# cpx-synth2-B.net
KiCad netlist of a schematic drawn in EAGLE
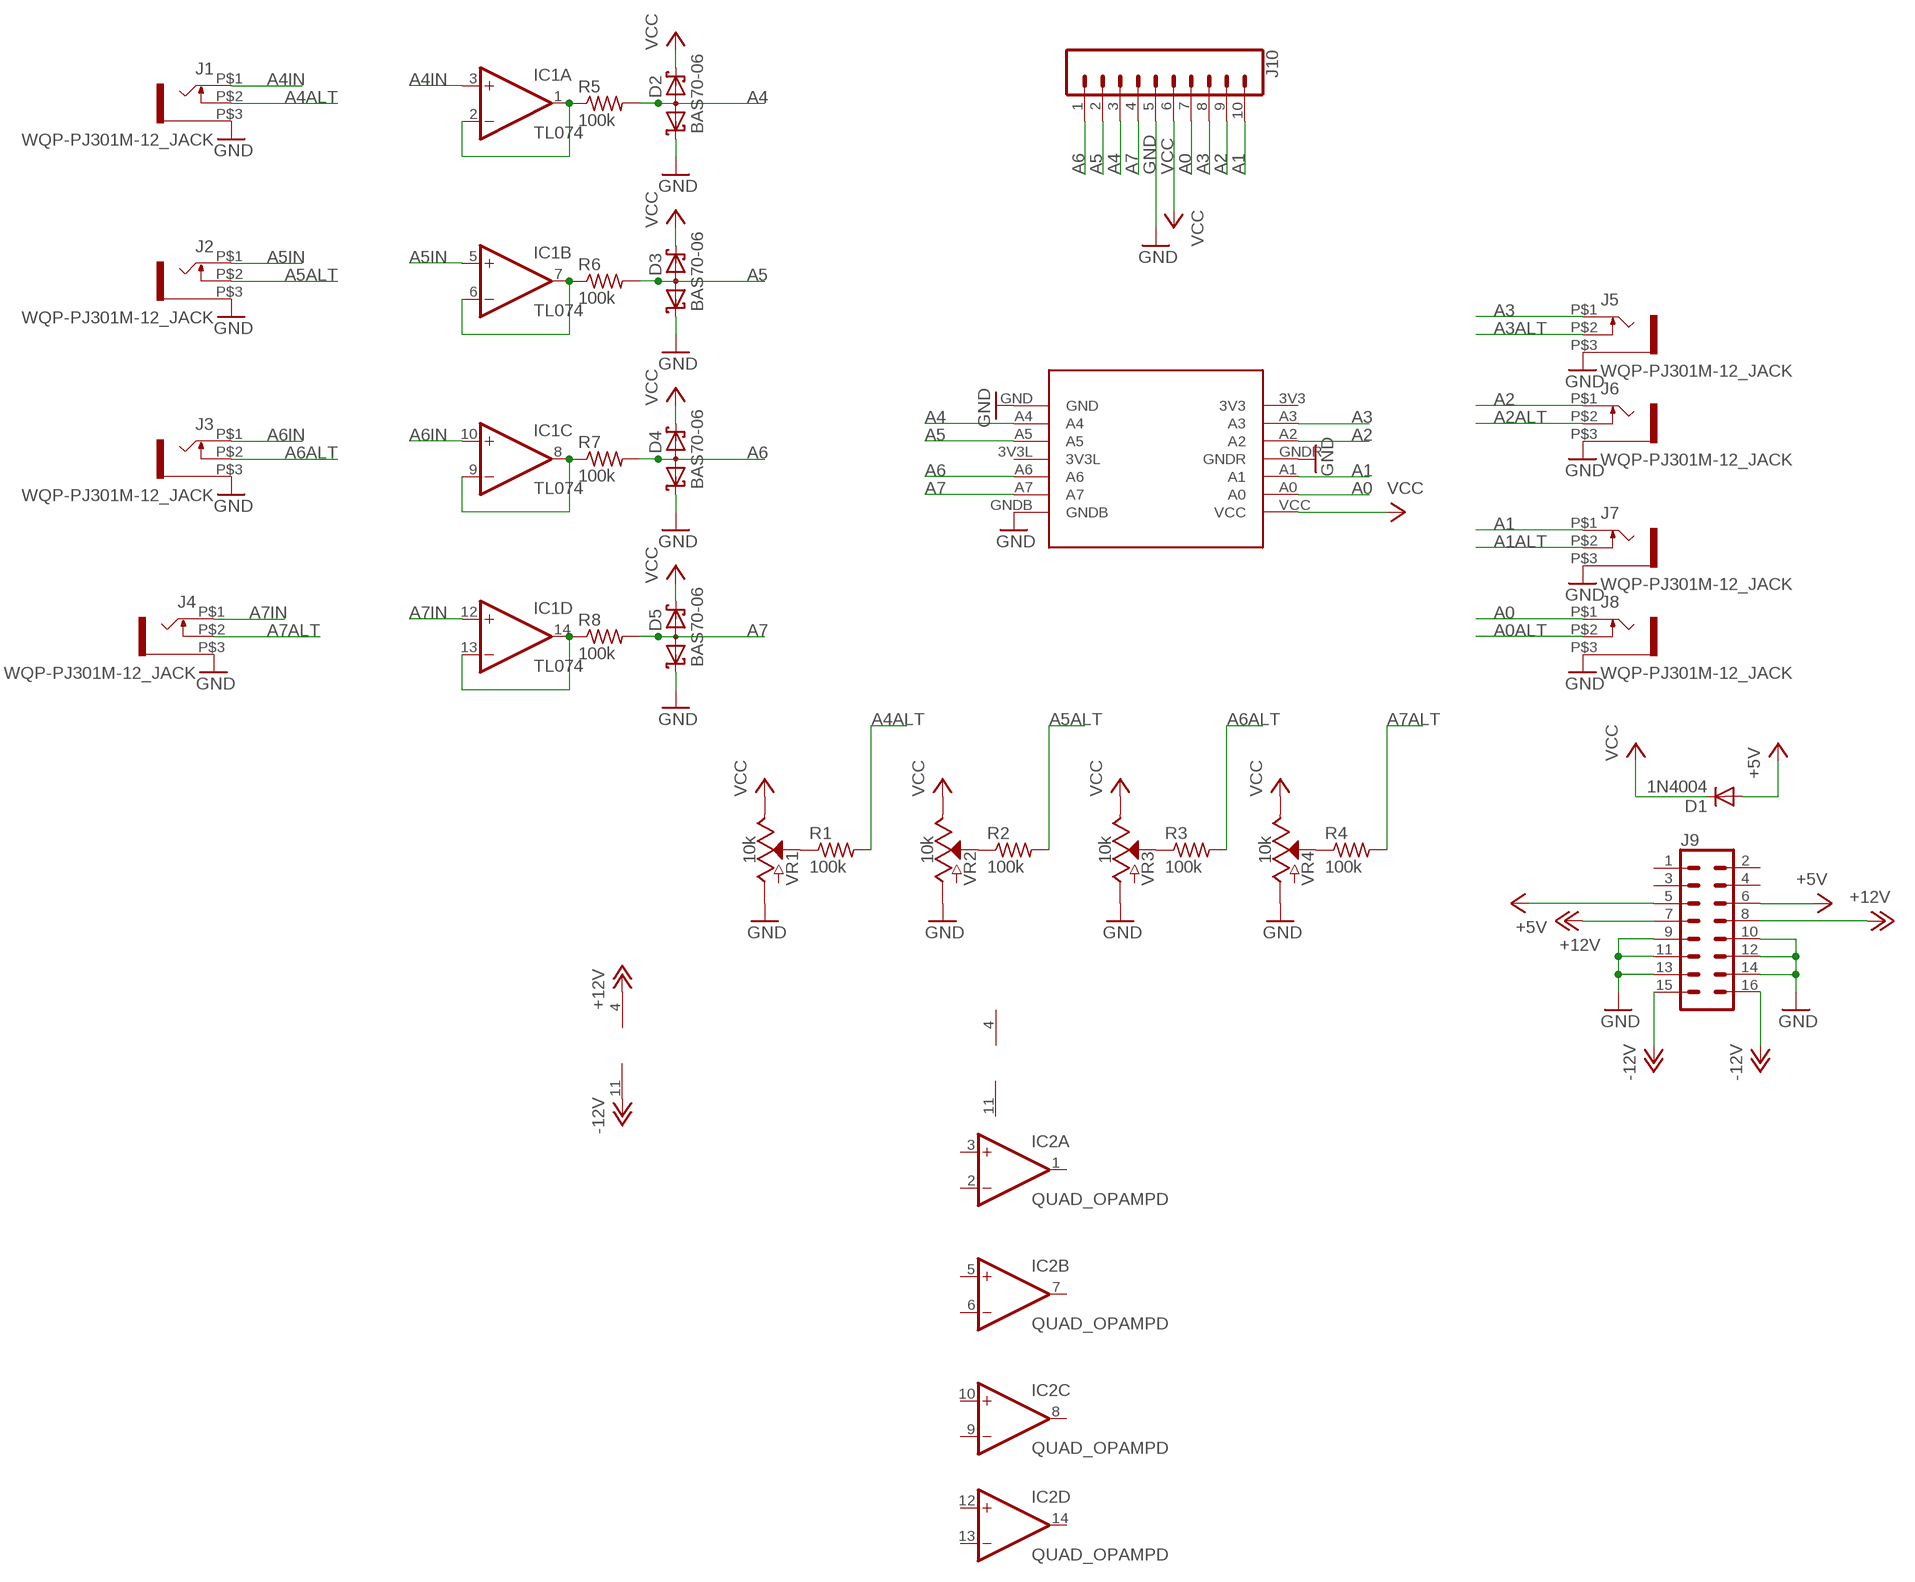
[diagram p0: schematic, sheet 1]

(export (version "E")
  (design (tool "Eeschema 10.0.6"))
  (components
    (comp (ref "D1")
      (value "1N4004")
      (footprint "eagle-import:DO41-10")
      (libsource (lib "eagle-import") (part "1N4004"))
    )
    (comp (ref "D2")
      (value "BAS70-06")
      (footprint "eagle-import:SOT23")
      (libsource (lib "eagle-import") (part "BAS70-06"))
    )
    (comp (ref "D3")
      (value "BAS70-06")
      (footprint "eagle-import:SOT23")
      (libsource (lib "eagle-import") (part "BAS70-06"))
    )
    (comp (ref "D4")
      (value "BAS70-06")
      (footprint "eagle-import:SOT23")
      (libsource (lib "eagle-import") (part "BAS70-06"))
    )
    (comp (ref "D5")
      (value "BAS70-06")
      (footprint "eagle-import:SOT23")
      (libsource (lib "eagle-import") (part "BAS70-06"))
    )
    (comp (ref "IC1")
      (value "TL074")
      (footprint "eagle-import:SO14")
      (libsource (lib "eagle-import") (part "QUAD_OPAMPD"))
    )
    (comp (ref "IC2")
      (value "QUAD_OPAMPD")
      (footprint "eagle-import:SO14")
      (libsource (lib "eagle-import") (part "QUAD_OPAMPD"))
    )
    (comp (ref "J1")
      (value "WQP-PJ301M-12_JACK")
      (footprint "eagle-import:WQP-PJ301M-12_JACK")
      (libsource (lib "eagle-import") (part "WQP-PJ301M-12_JACK"))
    )
    (comp (ref "J2")
      (value "WQP-PJ301M-12_JACK")
      (footprint "eagle-import:WQP-PJ301M-12_JACK")
      (libsource (lib "eagle-import") (part "WQP-PJ301M-12_JACK"))
    )
    (comp (ref "J3")
      (value "WQP-PJ301M-12_JACK")
      (footprint "eagle-import:WQP-PJ301M-12_JACK")
      (libsource (lib "eagle-import") (part "WQP-PJ301M-12_JACK"))
    )
    (comp (ref "J4")
      (value "WQP-PJ301M-12_JACK")
      (footprint "eagle-import:WQP-PJ301M-12_JACK")
      (libsource (lib "eagle-import") (part "WQP-PJ301M-12_JACK"))
    )
    (comp (ref "J5")
      (value "WQP-PJ301M-12_JACK")
      (footprint "eagle-import:WQP-PJ301M-12_JACK")
      (libsource (lib "eagle-import") (part "WQP-PJ301M-12_JACK"))
    )
    (comp (ref "J6")
      (value "WQP-PJ301M-12_JACK")
      (footprint "eagle-import:WQP-PJ301M-12_JACK")
      (libsource (lib "eagle-import") (part "WQP-PJ301M-12_JACK"))
    )
    (comp (ref "J7")
      (value "WQP-PJ301M-12_JACK")
      (footprint "eagle-import:WQP-PJ301M-12_JACK")
      (libsource (lib "eagle-import") (part "WQP-PJ301M-12_JACK"))
    )
    (comp (ref "J8")
      (value "WQP-PJ301M-12_JACK")
      (footprint "eagle-import:WQP-PJ301M-12_JACK")
      (libsource (lib "eagle-import") (part "WQP-PJ301M-12_JACK"))
    )
    (comp (ref "J9")
      (value "CONN_08X2")
      (footprint "eagle-import:2X8")
      (libsource (lib "eagle-import") (part "CONN_08X2"))
    )
    (comp (ref "J10")
      (value "CONN_10\"")
      (footprint "eagle-import:1X10")
      (libsource (lib "eagle-import") (part "CONN_10{dblquote}"))
    )
    (comp (ref "R1")
      (value "100k")
      (footprint "eagle-import:R0603")
      (libsource (lib "eagle-import") (part "R-US_R0603"))
    )
    (comp (ref "R2")
      (value "100k")
      (footprint "eagle-import:R0603")
      (libsource (lib "eagle-import") (part "R-US_R0603"))
    )
    (comp (ref "R3")
      (value "100k")
      (footprint "eagle-import:R0603")
      (libsource (lib "eagle-import") (part "R-US_R0603"))
    )
    (comp (ref "R4")
      (value "100k")
      (footprint "eagle-import:R0603")
      (libsource (lib "eagle-import") (part "R-US_R0603"))
    )
    (comp (ref "R5")
      (value "100k")
      (footprint "eagle-import:R0603")
      (libsource (lib "eagle-import") (part "R-US_R0603"))
    )
    (comp (ref "R6")
      (value "100k")
      (footprint "eagle-import:R0603")
      (libsource (lib "eagle-import") (part "R-US_R0603"))
    )
    (comp (ref "R7")
      (value "100k")
      (footprint "eagle-import:R0603")
      (libsource (lib "eagle-import") (part "R-US_R0603"))
    )
    (comp (ref "R8")
      (value "100k")
      (footprint "eagle-import:R0603")
      (libsource (lib "eagle-import") (part "R-US_R0603"))
    )
    (comp (ref "U1")
      (value "CIRCUITPLAYGROUNDEXPRESS")
      (footprint "eagle-import:CIRCUITPLAYGROUNDEXPRESS")
      (libsource (lib "eagle-import") (part "CIRCUITPLAYGROUNDEXPRESS"))
    )
    (comp (ref "VR1")
      (value "10k")
      (footprint "eagle-import:POT-PTH-ALPS-KIT")
      (libsource (lib "eagle-import") (part "POTENTIOMETER-PTH-9MM-1/20W-20%-KIT"))
    )
    (comp (ref "VR2")
      (value "10k")
      (footprint "eagle-import:POT-PTH-ALPS-KIT")
      (libsource (lib "eagle-import") (part "POTENTIOMETER-PTH-9MM-1/20W-20%-KIT"))
    )
    (comp (ref "VR3")
      (value "10k")
      (footprint "eagle-import:POT-PTH-ALPS-KIT")
      (libsource (lib "eagle-import") (part "POTENTIOMETER-PTH-9MM-1/20W-20%-KIT"))
    )
    (comp (ref "VR4")
      (value "10k")
      (footprint "eagle-import:POT-PTH-ALPS-KIT")
      (libsource (lib "eagle-import") (part "POTENTIOMETER-PTH-9MM-1/20W-20%-KIT"))
    )
  )
  (nets
    (net (code "1") (name "+5V") (class "Default")
      (node (ref "D1") (pin "A") (pinfunction "A_A") (pintype "passive"))
      (node (ref "J9") (pin "5") (pinfunction "5_5") (pintype "passive"))
      (node (ref "J9") (pin "6") (pinfunction "6_6") (pintype "passive"))
    )
    (net (code "2") (name "+12V") (class "Default")
      (node (ref "IC1") (pin "4") (pinfunction "V+_4") (pintype "power_in"))
      (node (ref "J9") (pin "7") (pinfunction "7_7") (pintype "passive"))
      (node (ref "J9") (pin "8") (pinfunction "8_8") (pintype "passive"))
    )
    (net (code "3") (name "-12V") (class "Default")
      (node (ref "IC1") (pin "11") (pinfunction "V-_11") (pintype "power_in"))
      (node (ref "J9") (pin "15") (pinfunction "15_15") (pintype "passive"))
      (node (ref "J9") (pin "16") (pinfunction "16_16") (pintype "passive"))
    )
    (net (code "4") (name "/A0") (class "Default")
      (node (ref "J10") (pin "7") (pinfunction "7_7") (pintype "passive"))
      (node (ref "J8") (pin "P$1") (pinfunction "2_P$1") (pintype "passive"))
      (node (ref "U1") (pin "A0") (pinfunction "A0_A0") (pintype "bidirectional"))
    )
    (net (code "5") (name "/A0ALT") (class "Default")
      (node (ref "J8") (pin "P$2") (pinfunction "3_P$2") (pintype "passive"))
    )
    (net (code "6") (name "/A1") (class "Default")
      (node (ref "J10") (pin "10") (pinfunction "10_10") (pintype "passive"))
      (node (ref "J7") (pin "P$1") (pinfunction "2_P$1") (pintype "passive"))
      (node (ref "U1") (pin "A1") (pinfunction "A1_A1") (pintype "bidirectional"))
    )
    (net (code "7") (name "/A1ALT") (class "Default")
      (node (ref "J7") (pin "P$2") (pinfunction "3_P$2") (pintype "passive"))
    )
    (net (code "8") (name "/A2") (class "Default")
      (node (ref "J10") (pin "9") (pinfunction "9_9") (pintype "passive"))
      (node (ref "J6") (pin "P$1") (pinfunction "2_P$1") (pintype "passive"))
      (node (ref "U1") (pin "A2") (pinfunction "A2_A2") (pintype "bidirectional"))
    )
    (net (code "9") (name "/A2ALT") (class "Default")
      (node (ref "J6") (pin "P$2") (pinfunction "3_P$2") (pintype "passive"))
    )
    (net (code "10") (name "/A3") (class "Default")
      (node (ref "J10") (pin "8") (pinfunction "8_8") (pintype "passive"))
      (node (ref "J5") (pin "P$1") (pinfunction "2_P$1") (pintype "passive"))
      (node (ref "U1") (pin "A3") (pinfunction "A3_A3") (pintype "bidirectional"))
    )
    (net (code "11") (name "/A3ALT") (class "Default")
      (node (ref "J5") (pin "P$2") (pinfunction "3_P$2") (pintype "passive"))
    )
    (net (code "12") (name "/A4") (class "Default")
      (node (ref "D2") (pin "3") (pinfunction "AA_3") (pintype "passive"))
      (node (ref "J10") (pin "3") (pinfunction "3_3") (pintype "passive"))
      (node (ref "R5") (pin "2") (pinfunction "2_2") (pintype "passive"))
      (node (ref "U1") (pin "A4") (pinfunction "A4_A4") (pintype "bidirectional"))
    )
    (net (code "13") (name "/A4ALT") (class "Default")
      (node (ref "J1") (pin "P$2") (pinfunction "3_P$2") (pintype "passive"))
      (node (ref "R1") (pin "2") (pinfunction "2_2") (pintype "passive"))
    )
    (net (code "14") (name "/A4IN") (class "Default")
      (node (ref "IC1") (pin "3") (pinfunction "+IN_3") (pintype "input"))
      (node (ref "J1") (pin "P$1") (pinfunction "2_P$1") (pintype "passive"))
    )
    (net (code "15") (name "/A5") (class "Default")
      (node (ref "D3") (pin "3") (pinfunction "AA_3") (pintype "passive"))
      (node (ref "J10") (pin "2") (pinfunction "2_2") (pintype "passive"))
      (node (ref "R6") (pin "2") (pinfunction "2_2") (pintype "passive"))
      (node (ref "U1") (pin "A5") (pinfunction "A5_A5") (pintype "bidirectional"))
    )
    (net (code "16") (name "/A5ALT") (class "Default")
      (node (ref "J2") (pin "P$2") (pinfunction "3_P$2") (pintype "passive"))
      (node (ref "R2") (pin "2") (pinfunction "2_2") (pintype "passive"))
    )
    (net (code "17") (name "/A5IN") (class "Default")
      (node (ref "IC1") (pin "5") (pinfunction "+IN_5") (pintype "input"))
      (node (ref "J2") (pin "P$1") (pinfunction "2_P$1") (pintype "passive"))
    )
    (net (code "18") (name "/A6") (class "Default")
      (node (ref "D4") (pin "3") (pinfunction "AA_3") (pintype "passive"))
      (node (ref "J10") (pin "1") (pinfunction "1_1") (pintype "passive"))
      (node (ref "R7") (pin "2") (pinfunction "2_2") (pintype "passive"))
      (node (ref "U1") (pin "A6") (pinfunction "A6_A6") (pintype "bidirectional"))
    )
    (net (code "19") (name "/A6ALT") (class "Default")
      (node (ref "J3") (pin "P$2") (pinfunction "3_P$2") (pintype "passive"))
      (node (ref "R3") (pin "2") (pinfunction "2_2") (pintype "passive"))
    )
    (net (code "20") (name "/A6IN") (class "Default")
      (node (ref "IC1") (pin "10") (pinfunction "+IN_10") (pintype "input"))
      (node (ref "J3") (pin "P$1") (pinfunction "2_P$1") (pintype "passive"))
    )
    (net (code "21") (name "/A7") (class "Default")
      (node (ref "D5") (pin "3") (pinfunction "AA_3") (pintype "passive"))
      (node (ref "J10") (pin "4") (pinfunction "4_4") (pintype "passive"))
      (node (ref "R8") (pin "2") (pinfunction "2_2") (pintype "passive"))
      (node (ref "U1") (pin "A7") (pinfunction "A7_A7") (pintype "bidirectional"))
    )
    (net (code "22") (name "/A7ALT") (class "Default")
      (node (ref "J4") (pin "P$2") (pinfunction "3_P$2") (pintype "passive"))
      (node (ref "R4") (pin "2") (pinfunction "2_2") (pintype "passive"))
    )
    (net (code "23") (name "/A7IN") (class "Default")
      (node (ref "IC1") (pin "12") (pinfunction "+IN_12") (pintype "input"))
      (node (ref "J4") (pin "P$1") (pinfunction "2_P$1") (pintype "passive"))
    )
    (net (code "24") (name "/V+") (class "Default")
      (node (ref "IC2") (pin "4") (pinfunction "V+_4") (pintype "power_in"))
    )
    (net (code "25") (name "/V-") (class "Default")
      (node (ref "IC2") (pin "11") (pinfunction "V-_11") (pintype "power_in"))
    )
    (net (code "26") (name "GND") (class "Default")
      (node (ref "D2") (pin "1") (pinfunction "K1_1") (pintype "passive"))
      (node (ref "D3") (pin "1") (pinfunction "K1_1") (pintype "passive"))
      (node (ref "D4") (pin "1") (pinfunction "K1_1") (pintype "passive"))
      (node (ref "D5") (pin "1") (pinfunction "K1_1") (pintype "passive"))
      (node (ref "J1") (pin "P$3") (pinfunction "1_P$3") (pintype "passive"))
      (node (ref "J10") (pin "5") (pinfunction "5_5") (pintype "passive"))
      (node (ref "J2") (pin "P$3") (pinfunction "1_P$3") (pintype "passive"))
      (node (ref "J3") (pin "P$3") (pinfunction "1_P$3") (pintype "passive"))
      (node (ref "J4") (pin "P$3") (pinfunction "1_P$3") (pintype "passive"))
      (node (ref "J5") (pin "P$3") (pinfunction "1_P$3") (pintype "passive"))
      (node (ref "J6") (pin "P$3") (pinfunction "1_P$3") (pintype "passive"))
      (node (ref "J7") (pin "P$3") (pinfunction "1_P$3") (pintype "passive"))
      (node (ref "J8") (pin "P$3") (pinfunction "1_P$3") (pintype "passive"))
      (node (ref "J9") (pin "10") (pinfunction "10_10") (pintype "passive"))
      (node (ref "J9") (pin "11") (pinfunction "11_11") (pintype "passive"))
      (node (ref "J9") (pin "12") (pinfunction "12_12") (pintype "passive"))
      (node (ref "J9") (pin "13") (pinfunction "13_13") (pintype "passive"))
      (node (ref "J9") (pin "14") (pinfunction "14_14") (pintype "passive"))
      (node (ref "J9") (pin "9") (pinfunction "9_9") (pintype "passive"))
      (node (ref "U1") (pin "GND") (pinfunction "GND_GND") (pintype "bidirectional"))
      (node (ref "U1") (pin "GNDB") (pinfunction "GNDB_GNDB") (pintype "bidirectional"))
      (node (ref "U1") (pin "GNDR") (pinfunction "GNDR_GNDR") (pintype "bidirectional"))
      (node (ref "VR1") (pin "P$3") (pinfunction "A_P$3") (pintype "passive"))
      (node (ref "VR2") (pin "P$3") (pinfunction "A_P$3") (pintype "passive"))
      (node (ref "VR3") (pin "P$3") (pinfunction "A_P$3") (pintype "passive"))
      (node (ref "VR4") (pin "P$3") (pinfunction "A_P$3") (pintype "passive"))
    )
    (net (code "27") (name "Net-(IC1A--IN)") (class "Default")
      (node (ref "IC1") (pin "1") (pinfunction "OUT_1") (pintype "output"))
      (node (ref "IC1") (pin "2") (pinfunction "-IN_2") (pintype "input"))
      (node (ref "R5") (pin "1") (pinfunction "1_1") (pintype "passive"))
    )
    (net (code "28") (name "Net-(IC1B--IN)") (class "Default")
      (node (ref "IC1") (pin "6") (pinfunction "-IN_6") (pintype "input"))
      (node (ref "IC1") (pin "7") (pinfunction "OUT_7") (pintype "output"))
      (node (ref "R6") (pin "1") (pinfunction "1_1") (pintype "passive"))
    )
    (net (code "29") (name "Net-(IC1C--IN)") (class "Default")
      (node (ref "IC1") (pin "8") (pinfunction "OUT_8") (pintype "output"))
      (node (ref "IC1") (pin "9") (pinfunction "-IN_9") (pintype "input"))
      (node (ref "R7") (pin "1") (pinfunction "1_1") (pintype "passive"))
    )
    (net (code "30") (name "Net-(IC1D--IN)") (class "Default")
      (node (ref "IC1") (pin "13") (pinfunction "-IN_13") (pintype "input"))
      (node (ref "IC1") (pin "14") (pinfunction "OUT_14") (pintype "output"))
      (node (ref "R8") (pin "1") (pinfunction "1_1") (pintype "passive"))
    )
    (net (code "31") (name "Net-(VR1-S)") (class "Default")
      (node (ref "R1") (pin "1") (pinfunction "1_1") (pintype "passive"))
      (node (ref "VR1") (pin "P$2") (pinfunction "S_P$2") (pintype "passive"))
    )
    (net (code "32") (name "Net-(VR2-S)") (class "Default")
      (node (ref "R2") (pin "1") (pinfunction "1_1") (pintype "passive"))
      (node (ref "VR2") (pin "P$2") (pinfunction "S_P$2") (pintype "passive"))
    )
    (net (code "33") (name "Net-(VR3-S)") (class "Default")
      (node (ref "R3") (pin "1") (pinfunction "1_1") (pintype "passive"))
      (node (ref "VR3") (pin "P$2") (pinfunction "S_P$2") (pintype "passive"))
    )
    (net (code "34") (name "Net-(VR4-S)") (class "Default")
      (node (ref "R4") (pin "1") (pinfunction "1_1") (pintype "passive"))
      (node (ref "VR4") (pin "P$2") (pinfunction "S_P$2") (pintype "passive"))
    )
    (net (code "35") (name "VCC") (class "Default")
      (node (ref "D1") (pin "C") (pinfunction "C_C") (pintype "passive"))
      (node (ref "D2") (pin "2") (pinfunction "K2_2") (pintype "passive"))
      (node (ref "D3") (pin "2") (pinfunction "K2_2") (pintype "passive"))
      (node (ref "D4") (pin "2") (pinfunction "K2_2") (pintype "passive"))
      (node (ref "D5") (pin "2") (pinfunction "K2_2") (pintype "passive"))
      (node (ref "J10") (pin "6") (pinfunction "6_6") (pintype "passive"))
      (node (ref "U1") (pin "VCC") (pinfunction "VCC_VCC") (pintype "bidirectional"))
      (node (ref "VR1") (pin "P$1") (pinfunction "E_P$1") (pintype "passive"))
      (node (ref "VR2") (pin "P$1") (pinfunction "E_P$1") (pintype "passive"))
      (node (ref "VR3") (pin "P$1") (pinfunction "E_P$1") (pintype "passive"))
      (node (ref "VR4") (pin "P$1") (pinfunction "E_P$1") (pintype "passive"))
    )
    (net (code "36") (name "unconnected-(IC2A-+IN-Pad3)") (class "Default")
      (node (ref "IC2") (pin "3") (pinfunction "+IN_3") (pintype "input"))
    )
    (net (code "37") (name "unconnected-(IC2A--IN-Pad2)") (class "Default")
      (node (ref "IC2") (pin "2") (pinfunction "-IN_2") (pintype "input"))
    )
    (net (code "38") (name "unconnected-(IC2A-OUT-Pad1)") (class "Default")
      (node (ref "IC2") (pin "1") (pinfunction "OUT_1") (pintype "output"))
    )
    (net (code "39") (name "unconnected-(IC2B-+IN-Pad5)") (class "Default")
      (node (ref "IC2") (pin "5") (pinfunction "+IN_5") (pintype "input"))
    )
    (net (code "40") (name "unconnected-(IC2B--IN-Pad6)") (class "Default")
      (node (ref "IC2") (pin "6") (pinfunction "-IN_6") (pintype "input"))
    )
    (net (code "41") (name "unconnected-(IC2B-OUT-Pad7)") (class "Default")
      (node (ref "IC2") (pin "7") (pinfunction "OUT_7") (pintype "output"))
    )
    (net (code "42") (name "unconnected-(IC2C-+IN-Pad10)") (class "Default")
      (node (ref "IC2") (pin "10") (pinfunction "+IN_10") (pintype "input"))
    )
    (net (code "43") (name "unconnected-(IC2C--IN-Pad9)") (class "Default")
      (node (ref "IC2") (pin "9") (pinfunction "-IN_9") (pintype "input"))
    )
    (net (code "44") (name "unconnected-(IC2C-OUT-Pad8)") (class "Default")
      (node (ref "IC2") (pin "8") (pinfunction "OUT_8") (pintype "output"))
    )
    (net (code "45") (name "unconnected-(IC2D-+IN-Pad12)") (class "Default")
      (node (ref "IC2") (pin "12") (pinfunction "+IN_12") (pintype "input"))
    )
    (net (code "46") (name "unconnected-(IC2D--IN-Pad13)") (class "Default")
      (node (ref "IC2") (pin "13") (pinfunction "-IN_13") (pintype "input"))
    )
    (net (code "47") (name "unconnected-(IC2D-OUT-Pad14)") (class "Default")
      (node (ref "IC2") (pin "14") (pinfunction "OUT_14") (pintype "output"))
    )
    (net (code "48") (name "unconnected-(J9-Pad1)") (class "Default")
      (node (ref "J9") (pin "1") (pinfunction "1_1") (pintype "passive"))
    )
    (net (code "49") (name "unconnected-(J9-Pad2)") (class "Default")
      (node (ref "J9") (pin "2") (pinfunction "2_2") (pintype "passive"))
    )
    (net (code "50") (name "unconnected-(J9-Pad3)") (class "Default")
      (node (ref "J9") (pin "3") (pinfunction "3_3") (pintype "passive"))
    )
    (net (code "51") (name "unconnected-(J9-Pad4)") (class "Default")
      (node (ref "J9") (pin "4") (pinfunction "4_4") (pintype "passive"))
    )
    (net (code "52") (name "unconnected-(U1-Pad3V3)") (class "Default")
      (node (ref "U1") (pin "3V3") (pinfunction "3V3_3V3") (pintype "bidirectional"))
    )
    (net (code "53") (name "unconnected-(U1-Pad3V3L)") (class "Default")
      (node (ref "U1") (pin "3V3L") (pinfunction "3V3L_3V3L") (pintype "bidirectional"))
    )
  )
)
